# MySens-GWeasySensRS485-V01-040.net
KiCad netlist of a schematic drawn in EAGLE
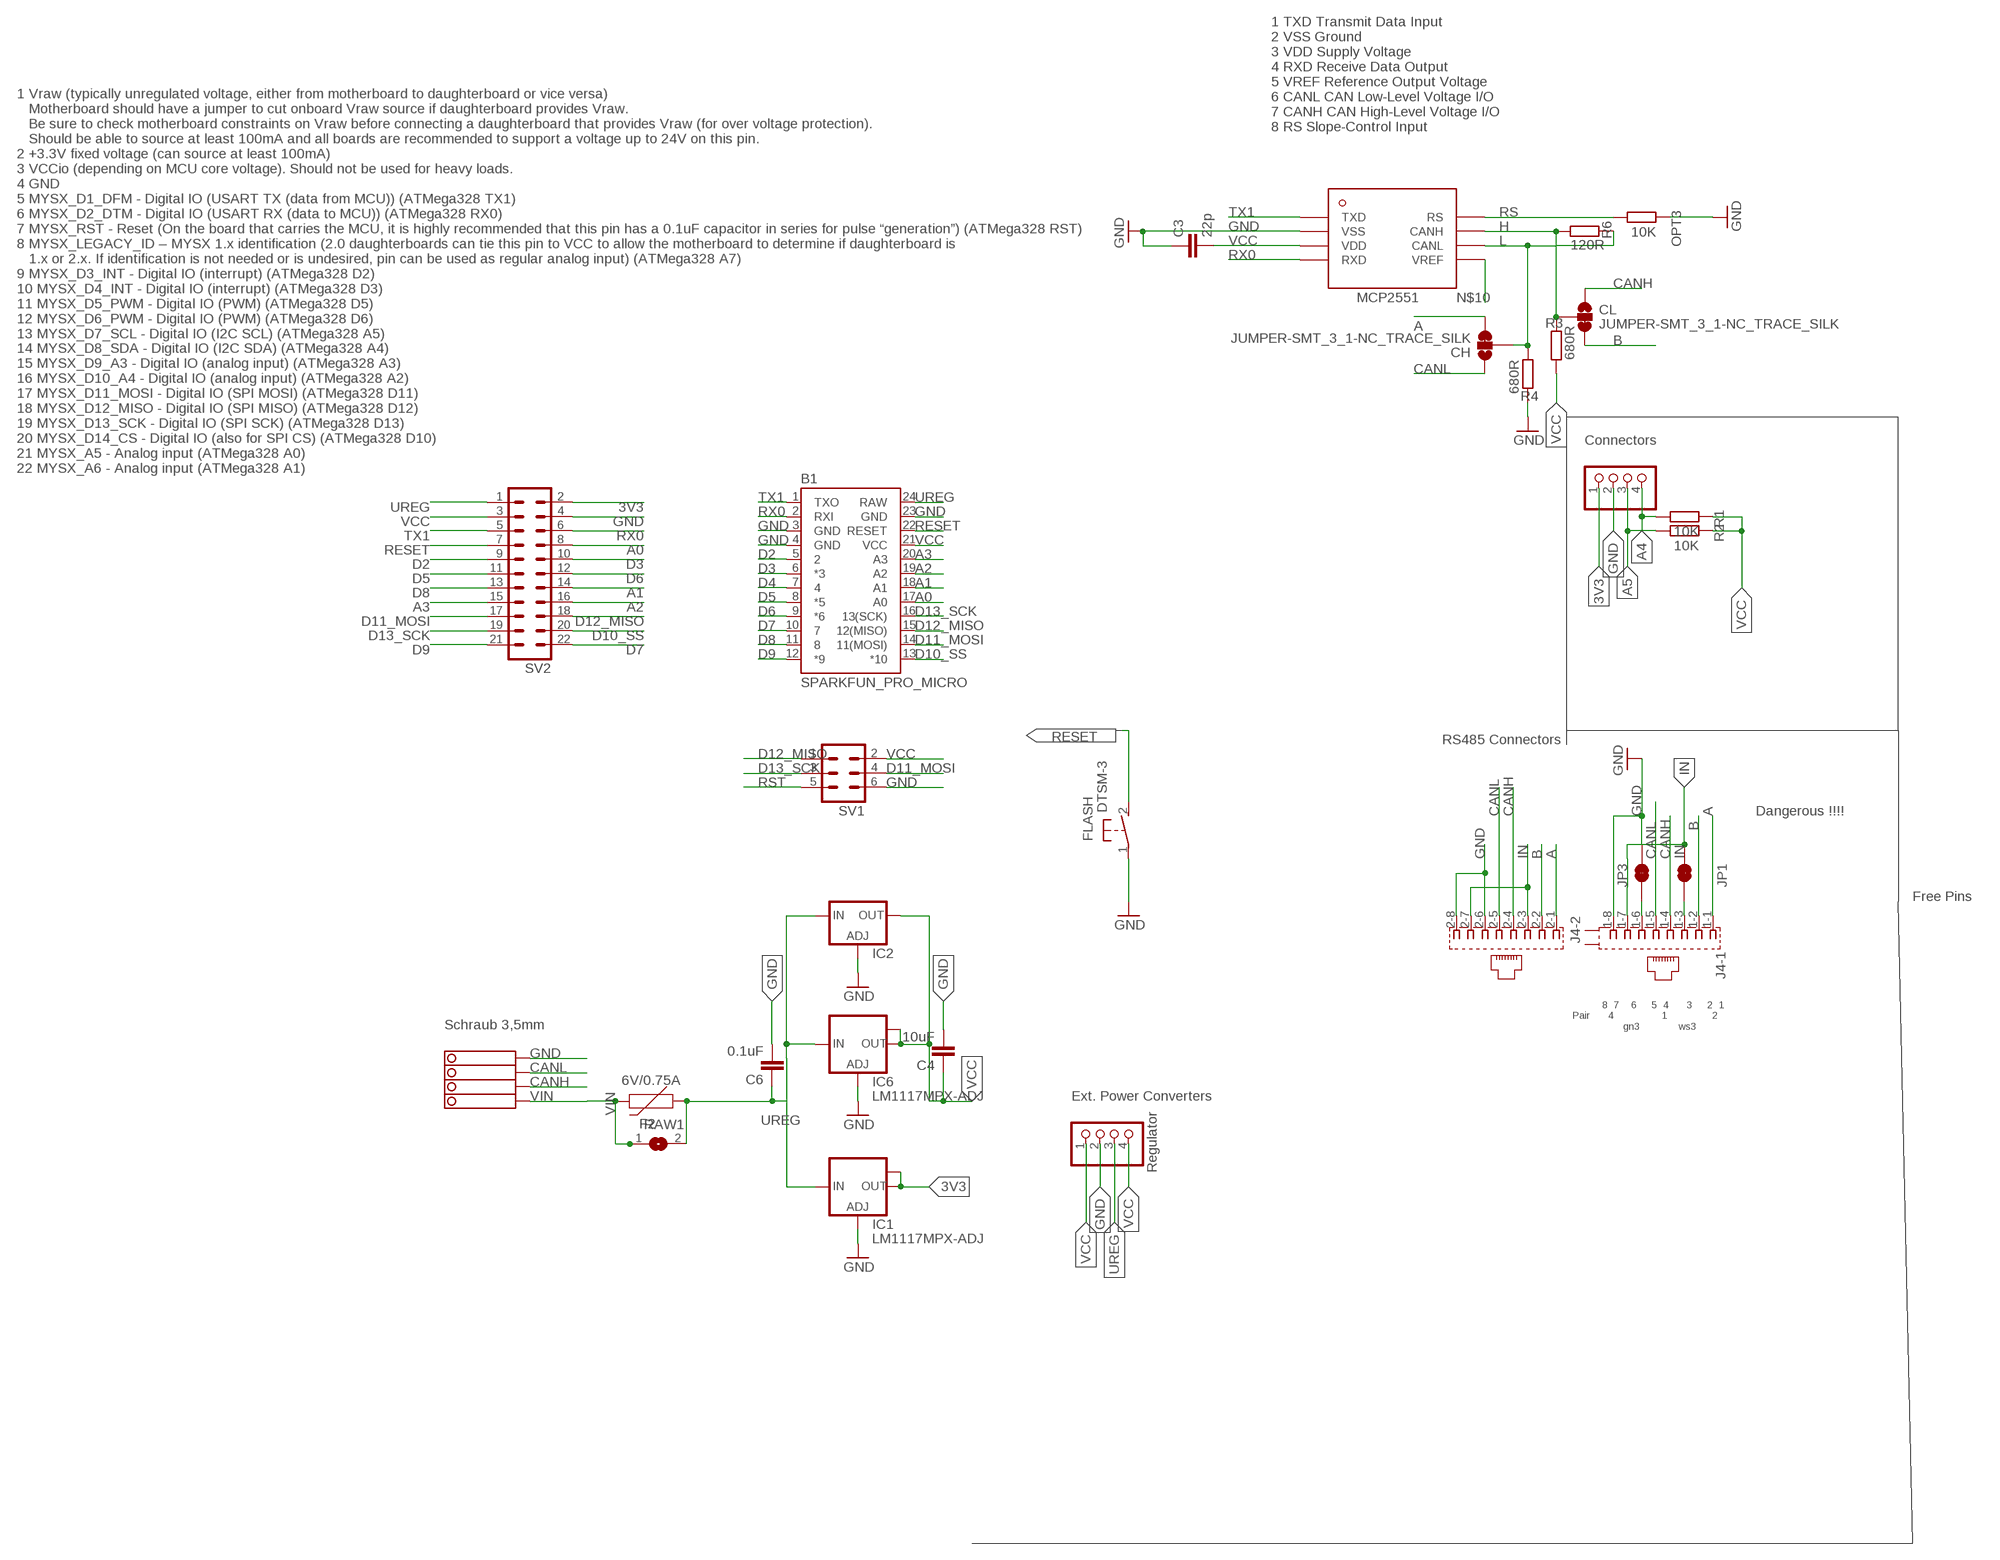
[diagram p0: schematic, sheet 1]

(export (version "E")
  (design (tool "Eeschema 10.0.6"))
  (components
    (comp (ref "B1")
      (value "SPARKFUN_PRO_MICRO")
      (footprint "eagle-import:SPARKFUN_PRO_MICRO")
      (libsource (lib "eagle-import") (part "SPARKFUN_PRO_MICRO"))
    )
    (comp (ref "C3")
      (value "22p")
      (footprint "eagle-import:C0805")
      (libsource (lib "eagle-import") (part "C-EUC0805"))
    )
    (comp (ref "C4")
      (value "10uF")
      (footprint "eagle-import:C1210")
      (libsource (lib "eagle-import") (part "C-EUC1210"))
    )
    (comp (ref "C6")
      (value "0.1uF")
      (footprint "eagle-import:C1206")
      (libsource (lib "eagle-import") (part "C-EUC1206"))
    )
    (comp (ref "CH")
      (value "JUMPER-SMT_3_1-NC_TRACE_SILK")
      (footprint "eagle-import:SMT-JUMPER_3_1-NC_TRACE_SILK")
      (libsource (lib "eagle-import") (part "JUMPER-SMT_3_1-NC_TRACE_SILK"))
    )
    (comp (ref "CL")
      (value "JUMPER-SMT_3_1-NC_TRACE_SILK")
      (footprint "eagle-import:SMT-JUMPER_3_1-NC_TRACE_SILK")
      (libsource (lib "eagle-import") (part "JUMPER-SMT_3_1-NC_TRACE_SILK"))
    )
    (comp (ref "F2")
      (value "6V/0.75A")
      (footprint "eagle-import:1206")
      (libsource (lib "eagle-import") (part "PPTC_THREE-QUARTER-AMP"))
    )
    (comp (ref "FLASH")
      (value "DTSM-3")
      (footprint "eagle-import:DTSM-3")
      (libsource (lib "eagle-import") (part "DTSM-3"))
    )
    (comp (ref "I2C")
      (value "PINHD-1X04_2.54-S")
      (footprint "eagle-import:1X04-S")
      (libsource (lib "eagle-import") (part "PINHD-1X04_2.54-S"))
    )
    (comp (ref "IC1")
      (value "LM1117MPX-ADJ")
      (footprint "eagle-import:SOT223")
      (libsource (lib "eagle-import") (part "LM1117MPX-ADJ"))
    )
    (comp (ref "IC2")
      (value "LD117ADT50TR")
      (footprint "eagle-import:DPACK")
      (libsource (lib "eagle-import") (part "LD117A?DT50TR"))
    )
    (comp (ref "IC6")
      (value "LM1117MPX-ADJ")
      (footprint "eagle-import:SOT223")
      (libsource (lib "eagle-import") (part "LM1117MPX-ADJ"))
    )
    (comp (ref "J4")
      (value "RJ45_2X_NARROW_SHILDPINS_NOCASE")
      (footprint "eagle-import:RJ45_2X_NARROW_SHILDPINS_NOCASE")
      (libsource (lib "eagle-import") (part "RJ45_2X_NARROW_SHILDPINS_NOCASE"))
    )
    (comp (ref "JP1")
      (value "JUMPER-SMT_2_NC_TRACE_SILK")
      (footprint "eagle-import:SMT-JUMPER_2_NC_TRACE_SILK")
      (libsource (lib "eagle-import") (part "JUMPER-SMT_2_NC_TRACE_SILK"))
    )
    (comp (ref "JP3")
      (value "JUMPER-SMT_2_NC_TRACE_SILK")
      (footprint "eagle-import:SMT-JUMPER_2_NC_TRACE_SILK")
      (libsource (lib "eagle-import") (part "JUMPER-SMT_2_NC_TRACE_SILK"))
    )
    (comp (ref "OPT3")
      (value "10K")
      (footprint "eagle-import:R0805")
      (libsource (lib "eagle-import") (part "R-EU_R0805"))
    )
    (comp (ref "R1")
      (value "10K")
      (footprint "eagle-import:R0805")
      (libsource (lib "eagle-import") (part "R-EU_R0805"))
    )
    (comp (ref "R2")
      (value "10K")
      (footprint "eagle-import:R0805")
      (libsource (lib "eagle-import") (part "R-EU_R0805"))
    )
    (comp (ref "R3")
      (value "680R")
      (footprint "eagle-import:R0805")
      (libsource (lib "eagle-import") (part "R-EU_R0805"))
    )
    (comp (ref "R4")
      (value "680R")
      (footprint "eagle-import:R0805")
      (libsource (lib "eagle-import") (part "R-EU_R0805"))
    )
    (comp (ref "R6")
      (value "120R")
      (footprint "eagle-import:R0805")
      (libsource (lib "eagle-import") (part "R-EU_R0805"))
    )
    (comp (ref "RAW1")
      (value "SJ")
      (footprint "eagle-import:SJ")
      (libsource (lib "eagle-import") (part "SJ"))
    )
    (comp (ref "STEPDWN")
      (value "PINHD-1X04_2.54-S")
      (footprint "eagle-import:1X04-S")
      (libsource (lib "eagle-import") (part "PINHD-1X04_2.54-S"))
    )
    (comp (ref "SV1")
      (value "MA03-2")
      (footprint "eagle-import:MA03-2")
      (libsource (lib "eagle-import") (part "MA03-2"))
    )
    (comp (ref "SV2")
      (value "MA11-2")
      (footprint "eagle-import:MA11-2")
      (libsource (lib "eagle-import") (part "MA11-2"))
    )
    (comp (ref "U$1")
      (value "MCP2551")
      (footprint "eagle-import:SOIC-8")
      (libsource (lib "eagle-import") (part "MCP2551"))
    )
    (comp (ref "X4")
      (value "1751264")
      (footprint "eagle-import:1751264")
      (libsource (lib "eagle-import") (part "1751264"))
    )
  )
  (nets
    (net (code "1") (name "/A") (class "Default")
      (node (ref "CH") (pin "3") (pinfunction "3_3") (pintype "passive"))
      (node (ref "J4") (pin "1-1") (pinfunction "1_1-1") (pintype "passive"))
      (node (ref "J4") (pin "2-1") (pinfunction "1_2-1") (pintype "passive"))
    )
    (net (code "2") (name "/A0") (class "Default")
      (node (ref "B1") (pin "17") (pinfunction "A0_17") (pintype "bidirectional"))
      (node (ref "SV2") (pin "8") (pinfunction "8_8") (pintype "passive"))
    )
    (net (code "3") (name "/A1") (class "Default")
      (node (ref "B1") (pin "18") (pinfunction "A1_18") (pintype "bidirectional"))
      (node (ref "SV2") (pin "14") (pinfunction "14_14") (pintype "passive"))
    )
    (net (code "4") (name "/A2") (class "Default")
      (node (ref "B1") (pin "19") (pinfunction "A2_19") (pintype "bidirectional"))
      (node (ref "SV2") (pin "16") (pinfunction "16_16") (pintype "passive"))
    )
    (net (code "5") (name "/A3") (class "Default")
      (node (ref "B1") (pin "20") (pinfunction "A3_20") (pintype "bidirectional"))
      (node (ref "SV2") (pin "15") (pinfunction "15_15") (pintype "passive"))
    )
    (net (code "6") (name "/B") (class "Default")
      (node (ref "CL") (pin "3") (pinfunction "3_3") (pintype "passive"))
      (node (ref "J4") (pin "1-2") (pinfunction "2_1-2") (pintype "passive"))
      (node (ref "J4") (pin "2-2") (pinfunction "2_2-2") (pintype "passive"))
    )
    (net (code "7") (name "/CANH") (class "Default")
      (node (ref "CL") (pin "1") (pinfunction "1_1") (pintype "passive"))
      (node (ref "J4") (pin "1-4") (pinfunction "4_1-4") (pintype "passive"))
      (node (ref "J4") (pin "2-4") (pinfunction "4_2-4") (pintype "passive"))
      (node (ref "X4") (pin "2") (pinfunction "K_2") (pintype "passive"))
    )
    (net (code "8") (name "/CANL") (class "Default")
      (node (ref "CH") (pin "1") (pinfunction "1_1") (pintype "passive"))
      (node (ref "J4") (pin "1-5") (pinfunction "5_1-5") (pintype "passive"))
      (node (ref "J4") (pin "2-5") (pinfunction "5_2-5") (pintype "passive"))
      (node (ref "X4") (pin "3") (pinfunction "K_3") (pintype "passive"))
    )
    (net (code "9") (name "/D2") (class "Default")
      (node (ref "B1") (pin "5") (pinfunction "2_5") (pintype "bidirectional"))
      (node (ref "SV2") (pin "9") (pinfunction "9_9") (pintype "passive"))
    )
    (net (code "10") (name "/D3") (class "Default")
      (node (ref "B1") (pin "6") (pinfunction "*3_6") (pintype "bidirectional"))
      (node (ref "SV2") (pin "10") (pinfunction "10_10") (pintype "passive"))
    )
    (net (code "11") (name "/D4") (class "Default")
      (node (ref "B1") (pin "7") (pinfunction "4_7") (pintype "bidirectional"))
    )
    (net (code "12") (name "/D5") (class "Default")
      (node (ref "B1") (pin "8") (pinfunction "*5_8") (pintype "bidirectional"))
      (node (ref "SV2") (pin "11") (pinfunction "11_11") (pintype "passive"))
    )
    (net (code "13") (name "/D6") (class "Default")
      (node (ref "B1") (pin "9") (pinfunction "*6_9") (pintype "bidirectional"))
      (node (ref "SV2") (pin "12") (pinfunction "12_12") (pintype "passive"))
    )
    (net (code "14") (name "/D7") (class "Default")
      (node (ref "B1") (pin "10") (pinfunction "7_10") (pintype "bidirectional"))
      (node (ref "SV2") (pin "22") (pinfunction "22_22") (pintype "passive"))
    )
    (net (code "15") (name "/D8") (class "Default")
      (node (ref "B1") (pin "11") (pinfunction "8_11") (pintype "bidirectional"))
      (node (ref "SV2") (pin "13") (pinfunction "13_13") (pintype "passive"))
    )
    (net (code "16") (name "/D9") (class "Default")
      (node (ref "B1") (pin "12") (pinfunction "*9_12") (pintype "bidirectional"))
      (node (ref "SV2") (pin "21") (pinfunction "21_21") (pintype "passive"))
    )
    (net (code "17") (name "/D10_SS") (class "Default")
      (node (ref "B1") (pin "13") (pinfunction "*10_13") (pintype "bidirectional"))
      (node (ref "SV2") (pin "20") (pinfunction "20_20") (pintype "passive"))
    )
    (net (code "18") (name "/D11_MOSI") (class "Default")
      (node (ref "B1") (pin "14") (pinfunction "11(MOSI)_14") (pintype "bidirectional"))
      (node (ref "SV1") (pin "4") (pinfunction "4_4") (pintype "passive"))
      (node (ref "SV2") (pin "17") (pinfunction "17_17") (pintype "passive"))
    )
    (net (code "19") (name "/D12_MISO") (class "Default")
      (node (ref "B1") (pin "15") (pinfunction "12(MISO)_15") (pintype "bidirectional"))
      (node (ref "SV1") (pin "1") (pinfunction "1_1") (pintype "passive"))
      (node (ref "SV2") (pin "18") (pinfunction "18_18") (pintype "passive"))
    )
    (net (code "20") (name "/D13_SCK") (class "Default")
      (node (ref "B1") (pin "16") (pinfunction "13(SCK)_16") (pintype "bidirectional"))
      (node (ref "SV1") (pin "3") (pinfunction "3_3") (pintype "passive"))
      (node (ref "SV2") (pin "19") (pinfunction "19_19") (pintype "passive"))
    )
    (net (code "21") (name "/H") (class "Default")
      (node (ref "CL") (pin "2") (pinfunction "2_2") (pintype "passive"))
      (node (ref "R3") (pin "2") (pinfunction "2_2") (pintype "passive"))
      (node (ref "R6") (pin "1") (pinfunction "1_1") (pintype "passive"))
      (node (ref "U$1") (pin "CANH") (pinfunction "CANH_CANH") (pintype "bidirectional"))
    )
    (net (code "22") (name "/L") (class "Default")
      (node (ref "CH") (pin "2") (pinfunction "2_2") (pintype "passive"))
      (node (ref "R4") (pin "1") (pinfunction "1_1") (pintype "passive"))
      (node (ref "R6") (pin "2") (pinfunction "2_2") (pintype "passive"))
      (node (ref "U$1") (pin "CANL") (pinfunction "CANL_CANL") (pintype "bidirectional"))
    )
    (net (code "23") (name "/N$10") (class "Default")
      (node (ref "U$1") (pin "VREF") (pinfunction "VREF_VREF") (pintype "bidirectional"))
    )
    (net (code "24") (name "/RESET") (class "Default")
      (node (ref "B1") (pin "22") (pinfunction "RESET_22") (pintype "bidirectional"))
      (node (ref "FLASH") (pin "2") (pinfunction "2_2") (pintype "passive"))
      (node (ref "SV2") (pin "7") (pinfunction "7_7") (pintype "passive"))
    )
    (net (code "25") (name "/RS") (class "Default")
      (node (ref "OPT3") (pin "2") (pinfunction "2_2") (pintype "passive"))
      (node (ref "U$1") (pin "RS") (pinfunction "RS_RS") (pintype "bidirectional"))
    )
    (net (code "26") (name "/RST") (class "Default")
      (node (ref "SV1") (pin "5") (pinfunction "5_5") (pintype "passive"))
    )
    (net (code "27") (name "/RX0") (class "Default")
      (node (ref "B1") (pin "2") (pinfunction "RXI_2") (pintype "bidirectional"))
      (node (ref "SV2") (pin "6") (pinfunction "6_6") (pintype "passive"))
      (node (ref "U$1") (pin "RXD") (pinfunction "RXD_RXD") (pintype "bidirectional"))
    )
    (net (code "28") (name "/TX1") (class "Default")
      (node (ref "B1") (pin "1") (pinfunction "TXO_1") (pintype "bidirectional"))
      (node (ref "SV2") (pin "5") (pinfunction "5_5") (pintype "passive"))
      (node (ref "U$1") (pin "TXD") (pinfunction "TXD_TXD") (pintype "bidirectional"))
    )
    (net (code "29") (name "/VIN") (class "Default")
      (node (ref "F2") (pin "2") (pinfunction "2_2") (pintype "bidirectional"))
      (node (ref "RAW1") (pin "1") (pinfunction "1_1") (pintype "passive"))
      (node (ref "X4") (pin "1") (pinfunction "K_1") (pintype "passive"))
    )
    (net (code "30") (name "3V3") (class "Default")
      (node (ref "I2C") (pin "1") (pinfunction "1_1") (pintype "passive"))
      (node (ref "IC1") (pin "2") (pinfunction "OUT_2") (pintype "passive"))
      (node (ref "IC1") (pin "TAB") (pinfunction "OUT1_TAB") (pintype "passive"))
      (node (ref "SV2") (pin "2") (pinfunction "2_2") (pintype "passive"))
    )
    (net (code "31") (name "A4") (class "Default")
      (node (ref "I2C") (pin "4") (pinfunction "4_4") (pintype "passive"))
      (node (ref "R1") (pin "2") (pinfunction "2_2") (pintype "passive"))
    )
    (net (code "32") (name "A5") (class "Default")
      (node (ref "I2C") (pin "3") (pinfunction "3_3") (pintype "passive"))
      (node (ref "R2") (pin "2") (pinfunction "2_2") (pintype "passive"))
    )
    (net (code "33") (name "GND") (class "Default")
      (node (ref "B1") (pin "23") (pinfunction "GND_23") (pintype "power_in"))
      (node (ref "B1") (pin "3") (pinfunction "GND_3") (pintype "power_in"))
      (node (ref "B1") (pin "4") (pinfunction "GND_4") (pintype "power_in"))
      (node (ref "C3") (pin "1") (pinfunction "1_1") (pintype "passive"))
      (node (ref "C4") (pin "2") (pinfunction "2_2") (pintype "passive"))
      (node (ref "C6") (pin "2") (pinfunction "2_2") (pintype "passive"))
      (node (ref "FLASH") (pin "1") (pinfunction "1_1") (pintype "passive"))
      (node (ref "I2C") (pin "2") (pinfunction "2_2") (pintype "passive"))
      (node (ref "IC1") (pin "1") (pinfunction "ADJ_1") (pintype "input"))
      (node (ref "IC2") (pin "1") (pinfunction "ADJ_1") (pintype "input"))
      (node (ref "IC6") (pin "1") (pinfunction "ADJ_1") (pintype "input"))
      (node (ref "J4") (pin "1-8") (pinfunction "8_1-8") (pintype "passive"))
      (node (ref "J4") (pin "2-6") (pinfunction "6_2-6") (pintype "passive"))
      (node (ref "J4") (pin "2-8") (pinfunction "8_2-8") (pintype "passive"))
      (node (ref "JP3") (pin "2") (pinfunction "2_2") (pintype "passive"))
      (node (ref "OPT3") (pin "1") (pinfunction "1_1") (pintype "passive"))
      (node (ref "R4") (pin "2") (pinfunction "2_2") (pintype "passive"))
      (node (ref "STEPDWN") (pin "2") (pinfunction "2_2") (pintype "passive"))
      (node (ref "SV1") (pin "6") (pinfunction "6_6") (pintype "passive"))
      (node (ref "SV2") (pin "4") (pinfunction "4_4") (pintype "passive"))
      (node (ref "U$1") (pin "VSS") (pinfunction "VSS_VSS") (pintype "bidirectional"))
      (node (ref "X4") (pin "4") (pinfunction "K_4") (pintype "passive"))
    )
    (net (code "34") (name "IN") (class "Default")
      (node (ref "J4") (pin "1-7") (pinfunction "7_1-7") (pintype "passive"))
      (node (ref "J4") (pin "2-3") (pinfunction "3_2-3") (pintype "passive"))
      (node (ref "J4") (pin "2-7") (pinfunction "7_2-7") (pintype "passive"))
      (node (ref "JP1") (pin "2") (pinfunction "2_2") (pintype "passive"))
    )
    (net (code "35") (name "Net-(J4A-3)") (class "Default")
      (node (ref "J4") (pin "1-3") (pinfunction "3_1-3") (pintype "passive"))
      (node (ref "JP1") (pin "1") (pinfunction "1_1") (pintype "passive"))
    )
    (net (code "36") (name "Net-(J4A-6)") (class "Default")
      (node (ref "J4") (pin "1-6") (pinfunction "6_1-6") (pintype "passive"))
      (node (ref "JP3") (pin "1") (pinfunction "1_1") (pintype "passive"))
    )
    (net (code "37") (name "UREG") (class "Default")
      (node (ref "B1") (pin "24") (pinfunction "RAW_24") (pintype "power_in"))
      (node (ref "C6") (pin "1") (pinfunction "1_1") (pintype "passive"))
      (node (ref "F2") (pin "1") (pinfunction "1_1") (pintype "bidirectional"))
      (node (ref "IC1") (pin "3") (pinfunction "IN_3") (pintype "input"))
      (node (ref "IC2") (pin "3") (pinfunction "IN_3") (pintype "input"))
      (node (ref "IC6") (pin "3") (pinfunction "IN_3") (pintype "input"))
      (node (ref "RAW1") (pin "2") (pinfunction "2_2") (pintype "passive"))
      (node (ref "STEPDWN") (pin "3") (pinfunction "3_3") (pintype "passive"))
      (node (ref "SV2") (pin "1") (pinfunction "1_1") (pintype "passive"))
    )
    (net (code "38") (name "VCC") (class "Default")
      (node (ref "B1") (pin "21") (pinfunction "VCC_21") (pintype "power_in"))
      (node (ref "C3") (pin "2") (pinfunction "2_2") (pintype "passive"))
      (node (ref "C4") (pin "1") (pinfunction "1_1") (pintype "passive"))
      (node (ref "IC2") (pin "4") (pinfunction "OUT_4") (pintype "passive"))
      (node (ref "IC6") (pin "2") (pinfunction "OUT_2") (pintype "passive"))
      (node (ref "IC6") (pin "TAB") (pinfunction "OUT1_TAB") (pintype "passive"))
      (node (ref "R1") (pin "1") (pinfunction "1_1") (pintype "passive"))
      (node (ref "R2") (pin "1") (pinfunction "1_1") (pintype "passive"))
      (node (ref "R3") (pin "1") (pinfunction "1_1") (pintype "passive"))
      (node (ref "STEPDWN") (pin "1") (pinfunction "1_1") (pintype "passive"))
      (node (ref "STEPDWN") (pin "4") (pinfunction "4_4") (pintype "passive"))
      (node (ref "SV1") (pin "2") (pinfunction "2_2") (pintype "passive"))
      (node (ref "SV2") (pin "3") (pinfunction "3_3") (pintype "passive"))
      (node (ref "U$1") (pin "VDD") (pinfunction "VDD_VDD") (pintype "bidirectional"))
    )
    (net (code "39") (name "unconnected-(J4A-S1-PadG1)") (class "Default")
      (node (ref "J4") (pin "G1") (pinfunction "S1_G1") (pintype "passive"))
    )
    (net (code "40") (name "unconnected-(J4A-S2-PadG3)") (class "Default")
      (node (ref "J4") (pin "G3") (pinfunction "S2_G3") (pintype "passive"))
    )
  )
)
